# supply_test.net
KiCad netlist of a schematic drawn in EAGLE
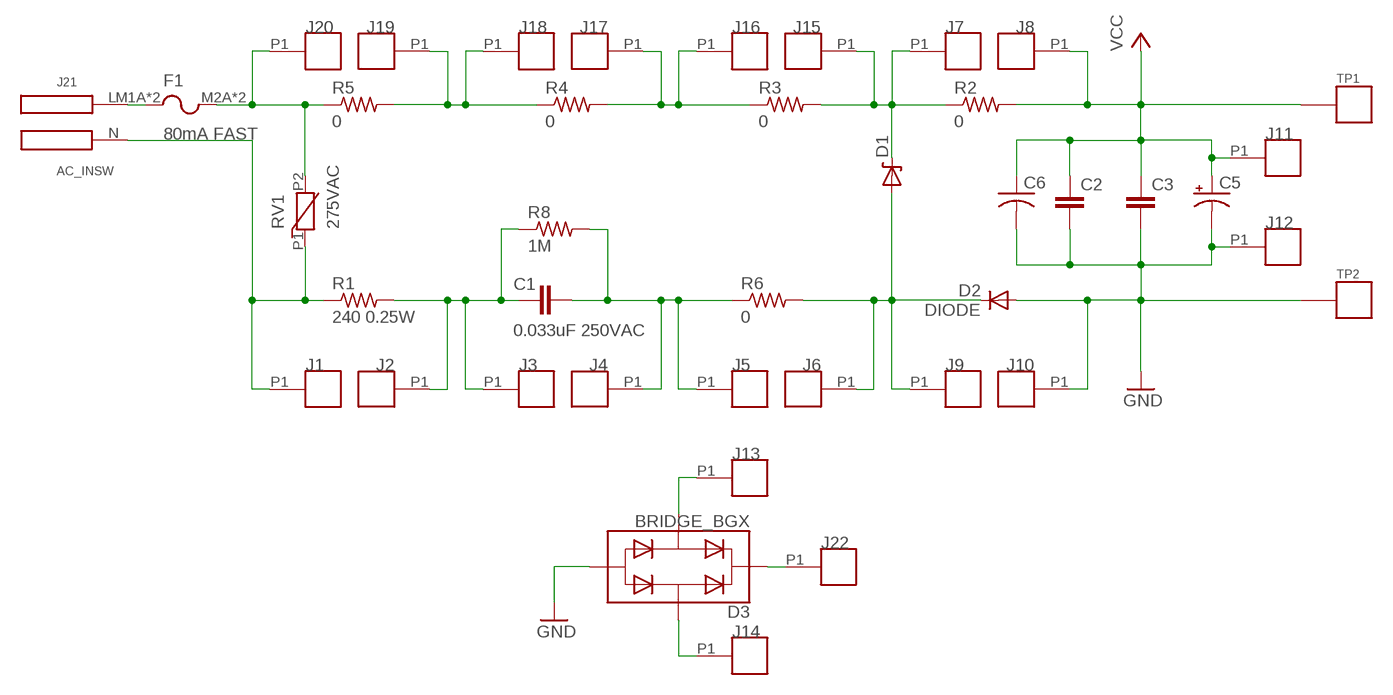
[diagram p0: schematic, sheet 1]
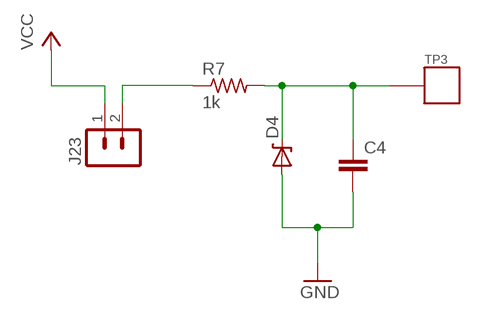
[diagram p1: schematic, sheet 2]

(export (version "E")
  (design (tool "Eeschema 10.0.6"))
  (components
    (comp (ref "C4")
      (value "C-EUC0603")
      (footprint "eagle-import:C0603")
      (libsource (lib "eagle-import") (part "C-EUC0603"))
    )
    (comp (ref "D4")
      (value "ZENERBZT52")
      (footprint "eagle-import:BZT52")
      (libsource (lib "eagle-import") (part "ZENERBZT52"))
    )
    (comp (ref "J23")
      (value "MA02-1STR")
      (footprint "eagle-import:MA02-1")
      (libsource (lib "eagle-import") (part "MA02-1STR"))
    )
    (comp (ref "R7")
      (value "1k")
      (footprint "eagle-import:R0603")
      (libsource (lib "eagle-import") (part "R-US_R0603"))
    )
    (comp (ref "TP3")
      (value "TP_STD")
      (footprint "eagle-import:TP")
      (libsource (lib "eagle-import") (part "TP_STD"))
    )
    (comp (ref "C1")
      (value "0.033uF 250VAC")
      (footprint "eagle-import:C2220K")
      (libsource (lib "eagle-import") (part "C-EUC2220K"))
    )
    (comp (ref "C2")
      (value "C-EUC0805")
      (footprint "eagle-import:C0805")
      (libsource (lib "eagle-import") (part "C-EUC0805"))
    )
    (comp (ref "C3")
      (value "C-EUC0603")
      (footprint "eagle-import:C0603")
      (libsource (lib "eagle-import") (part "C-EUC0603"))
    )
    (comp (ref "C5")
      (value "CAP_POL1206")
      (footprint "eagle-import:EIA3216")
      (libsource (lib "eagle-import") (part "CAP_POL1206"))
    )
    (comp (ref "C6")
      (value "C-USC1210")
      (footprint "eagle-import:C1210")
      (libsource (lib "eagle-import") (part "C-USC1210"))
    )
    (comp (ref "D1")
      (value "ZENERBZT52")
      (footprint "eagle-import:BZT52")
      (libsource (lib "eagle-import") (part "ZENERBZT52"))
    )
    (comp (ref "D2")
      (value "DIODE")
      (footprint "eagle-import:BAS521")
      (libsource (lib "eagle-import") (part "DIODE"))
    )
    (comp (ref "D3")
      (value "BRIDGE_BGX")
      (footprint "eagle-import:TO-253-4")
      (libsource (lib "eagle-import") (part "BRIDGE_BGX"))
    )
    (comp (ref "F1")
      (value "80mA FAST")
      (footprint "eagle-import:FUSE")
      (libsource (lib "eagle-import") (part "FUSE"))
    )
    (comp (ref "J1")
      (value "SOCKET")
      (footprint "eagle-import:SOCKET_1MM")
      (libsource (lib "eagle-import") (part "SOCKET"))
    )
    (comp (ref "J2")
      (value "SOCKET")
      (footprint "eagle-import:SOCKET_1MM")
      (libsource (lib "eagle-import") (part "SOCKET"))
    )
    (comp (ref "J3")
      (value "SOCKET")
      (footprint "eagle-import:SOCKET_1MM")
      (libsource (lib "eagle-import") (part "SOCKET"))
    )
    (comp (ref "J4")
      (value "SOCKET")
      (footprint "eagle-import:SOCKET_1MM")
      (libsource (lib "eagle-import") (part "SOCKET"))
    )
    (comp (ref "J5")
      (value "SOCKET")
      (footprint "eagle-import:SOCKET_1MM")
      (libsource (lib "eagle-import") (part "SOCKET"))
    )
    (comp (ref "J6")
      (value "SOCKET")
      (footprint "eagle-import:SOCKET_1MM")
      (libsource (lib "eagle-import") (part "SOCKET"))
    )
    (comp (ref "J7")
      (value "SOCKET")
      (footprint "eagle-import:SOCKET_1MM")
      (libsource (lib "eagle-import") (part "SOCKET"))
    )
    (comp (ref "J8")
      (value "SOCKET")
      (footprint "eagle-import:SOCKET_1MM")
      (libsource (lib "eagle-import") (part "SOCKET"))
    )
    (comp (ref "J9")
      (value "SOCKET")
      (footprint "eagle-import:SOCKET_1MM")
      (libsource (lib "eagle-import") (part "SOCKET"))
    )
    (comp (ref "J10")
      (value "SOCKET")
      (footprint "eagle-import:SOCKET_1MM")
      (libsource (lib "eagle-import") (part "SOCKET"))
    )
    (comp (ref "J11")
      (value "SOCKET")
      (footprint "eagle-import:SOCKET_1MM")
      (libsource (lib "eagle-import") (part "SOCKET"))
    )
    (comp (ref "J12")
      (value "SOCKET")
      (footprint "eagle-import:SOCKET_1MM")
      (libsource (lib "eagle-import") (part "SOCKET"))
    )
    (comp (ref "J13")
      (value "SOCKET")
      (footprint "eagle-import:SOCKET_1MM")
      (fields (field (name "DIGIKEY") "ED90076-ND"))
      (libsource (lib "eagle-import") (part "SOCKET"))
    )
    (comp (ref "J14")
      (value "SOCKET")
      (footprint "eagle-import:SOCKET_1MM")
      (fields (field (name "DIGIKEY") "ED90076-ND"))
      (libsource (lib "eagle-import") (part "SOCKET"))
    )
    (comp (ref "J15")
      (value "SOCKET")
      (footprint "eagle-import:SOCKET_1MM")
      (libsource (lib "eagle-import") (part "SOCKET"))
    )
    (comp (ref "J16")
      (value "SOCKET")
      (footprint "eagle-import:SOCKET_1MM")
      (libsource (lib "eagle-import") (part "SOCKET"))
    )
    (comp (ref "J17")
      (value "SOCKET")
      (footprint "eagle-import:SOCKET_1MM")
      (libsource (lib "eagle-import") (part "SOCKET"))
    )
    (comp (ref "J18")
      (value "SOCKET")
      (footprint "eagle-import:SOCKET_1MM")
      (libsource (lib "eagle-import") (part "SOCKET"))
    )
    (comp (ref "J19")
      (value "SOCKET")
      (footprint "eagle-import:SOCKET_1MM")
      (libsource (lib "eagle-import") (part "SOCKET"))
    )
    (comp (ref "J20")
      (value "SOCKET")
      (footprint "eagle-import:SOCKET_1MM")
      (libsource (lib "eagle-import") (part "SOCKET"))
    )
    (comp (ref "J21")
      (value "AC_INSW")
      (footprint "eagle-import:AC_DC21")
      (libsource (lib "eagle-import") (part "AC_INSW"))
    )
    (comp (ref "J22")
      (value "SOCKET")
      (footprint "eagle-import:SOCKET_1MM")
      (fields (field (name "DIGIKEY") "ED90076-ND"))
      (libsource (lib "eagle-import") (part "SOCKET"))
    )
    (comp (ref "R1")
      (value "240 0.25W")
      (footprint "eagle-import:R0603")
      (libsource (lib "eagle-import") (part "R-US_R0603"))
    )
    (comp (ref "R2")
      (value "0")
      (footprint "eagle-import:R0603")
      (libsource (lib "eagle-import") (part "R-US_R0603"))
    )
    (comp (ref "R3")
      (value "0")
      (footprint "eagle-import:R0603")
      (libsource (lib "eagle-import") (part "R-US_R0603"))
    )
    (comp (ref "R4")
      (value "0")
      (footprint "eagle-import:R0603")
      (libsource (lib "eagle-import") (part "R-US_R0603"))
    )
    (comp (ref "R5")
      (value "0")
      (footprint "eagle-import:R0603")
      (libsource (lib "eagle-import") (part "R-US_R0603"))
    )
    (comp (ref "R6")
      (value "0")
      (footprint "eagle-import:R0603")
      (libsource (lib "eagle-import") (part "R-US_R0603"))
    )
    (comp (ref "R8")
      (value "1M")
      (footprint "eagle-import:R0603")
      (libsource (lib "eagle-import") (part "R-US_R0603"))
    )
    (comp (ref "RV1")
      (value "275VAC")
      (footprint "eagle-import:MOV_4032")
      (libsource (lib "eagle-import") (part "MOV_CU4032"))
    )
    (comp (ref "TP1")
      (value "TP_STD")
      (footprint "eagle-import:TP")
      (libsource (lib "eagle-import") (part "TP_STD"))
    )
    (comp (ref "TP2")
      (value "TP_STD")
      (footprint "eagle-import:TP")
      (libsource (lib "eagle-import") (part "TP_STD"))
    )
  )
  (nets
    (net (code "1") (name "GND") (class "Default")
      (node (ref "C2") (pin "2") (pinfunction "2_2") (pintype "passive"))
      (node (ref "C3") (pin "2") (pinfunction "2_2") (pintype "passive"))
      (node (ref "C4") (pin "2") (pinfunction "2_2") (pintype "passive"))
      (node (ref "C5") (pin "C") (pinfunction "-_C") (pintype "passive"))
      (node (ref "C6") (pin "2") (pinfunction "2_2") (pintype "passive"))
      (node (ref "D2") (pin "A") (pinfunction "A_A") (pintype "passive"))
      (node (ref "D3") (pin "P3") (pinfunction "P3_P3") (pintype "passive"))
      (node (ref "D4") (pin "A") (pinfunction "A_A") (pintype "passive"))
      (node (ref "J10") (pin "P1") (pinfunction "P1_P1") (pintype "bidirectional"))
      (node (ref "J12") (pin "P1") (pinfunction "P1_P1") (pintype "bidirectional"))
      (node (ref "TP2") (pin "P$1") (pinfunction "P$1_P$1") (pintype "bidirectional"))
    )
    (net (code "2") (name "Net-(C1-Pad1)") (class "Default")
      (node (ref "C1") (pin "1") (pinfunction "1_1") (pintype "passive"))
      (node (ref "J4") (pin "P1") (pinfunction "P1_P1") (pintype "bidirectional"))
      (node (ref "J5") (pin "P1") (pinfunction "P1_P1") (pintype "bidirectional"))
      (node (ref "R6") (pin "1") (pinfunction "1_1") (pintype "passive"))
      (node (ref "R8") (pin "2") (pinfunction "2_2") (pintype "passive"))
    )
    (net (code "3") (name "Net-(C1-Pad2)") (class "Default")
      (node (ref "C1") (pin "2") (pinfunction "2_2") (pintype "passive"))
      (node (ref "J2") (pin "P1") (pinfunction "P1_P1") (pintype "bidirectional"))
      (node (ref "J3") (pin "P1") (pinfunction "P1_P1") (pintype "bidirectional"))
      (node (ref "R1") (pin "2") (pinfunction "2_2") (pintype "passive"))
      (node (ref "R8") (pin "1") (pinfunction "1_1") (pintype "passive"))
    )
    (net (code "4") (name "Net-(C4-Pad1)") (class "Default")
      (node (ref "C4") (pin "1") (pinfunction "1_1") (pintype "passive"))
      (node (ref "D4") (pin "C") (pinfunction "C_C") (pintype "passive"))
      (node (ref "R7") (pin "2") (pinfunction "2_2") (pintype "passive"))
      (node (ref "TP3") (pin "P$1") (pinfunction "P$1_P$1") (pintype "bidirectional"))
    )
    (net (code "5") (name "Net-(D1-PadA)") (class "Default")
      (node (ref "D1") (pin "A") (pinfunction "A_A") (pintype "passive"))
      (node (ref "D2") (pin "C") (pinfunction "C_C") (pintype "passive"))
      (node (ref "J6") (pin "P1") (pinfunction "P1_P1") (pintype "bidirectional"))
      (node (ref "J9") (pin "P1") (pinfunction "P1_P1") (pintype "bidirectional"))
      (node (ref "R6") (pin "2") (pinfunction "2_2") (pintype "passive"))
    )
    (net (code "6") (name "Net-(D1-PadC)") (class "Default")
      (node (ref "D1") (pin "C") (pinfunction "C_C") (pintype "passive"))
      (node (ref "J15") (pin "P1") (pinfunction "P1_P1") (pintype "bidirectional"))
      (node (ref "J7") (pin "P1") (pinfunction "P1_P1") (pintype "bidirectional"))
      (node (ref "R2") (pin "1") (pinfunction "1_1") (pintype "passive"))
      (node (ref "R3") (pin "2") (pinfunction "2_2") (pintype "passive"))
    )
    (net (code "7") (name "Net-(D3-PadP1)") (class "Default")
      (node (ref "D3") (pin "P1") (pinfunction "P1_P1") (pintype "passive"))
      (node (ref "J22") (pin "P1") (pinfunction "P1_P1") (pintype "bidirectional"))
    )
    (net (code "8") (name "Net-(D3-PadP2)") (class "Default")
      (node (ref "D3") (pin "P2") (pinfunction "P2_P2") (pintype "passive"))
      (node (ref "J13") (pin "P1") (pinfunction "P1_P1") (pintype "bidirectional"))
    )
    (net (code "9") (name "Net-(D3-PadP4)") (class "Default")
      (node (ref "D3") (pin "P4") (pinfunction "P4_P4") (pintype "passive"))
      (node (ref "J14") (pin "P1") (pinfunction "P1_P1") (pintype "bidirectional"))
    )
    (net (code "10") (name "Net-(F1-P2-PadM2A)") (class "Default")
      (node (ref "F1") (pin "M2A") (pinfunction "P2_M2A") (pintype "bidirectional"))
      (node (ref "F1") (pin "M2B") (pinfunction "P2_M2B") (pintype "bidirectional"))
      (node (ref "J20") (pin "P1") (pinfunction "P1_P1") (pintype "bidirectional"))
      (node (ref "R5") (pin "1") (pinfunction "1_1") (pintype "passive"))
      (node (ref "RV1") (pin "P2") (pinfunction "P2_P2") (pintype "bidirectional"))
    )
    (net (code "11") (name "Net-(J1-PadP1)") (class "Default")
      (node (ref "J1") (pin "P1") (pinfunction "P1_P1") (pintype "bidirectional"))
      (node (ref "J21") (pin "N") (pinfunction "N_N") (pintype "bidirectional"))
      (node (ref "R1") (pin "1") (pinfunction "1_1") (pintype "passive"))
      (node (ref "RV1") (pin "P1") (pinfunction "P1_P1") (pintype "bidirectional"))
    )
    (net (code "12") (name "Net-(J16-PadP1)") (class "Default")
      (node (ref "J16") (pin "P1") (pinfunction "P1_P1") (pintype "bidirectional"))
      (node (ref "J17") (pin "P1") (pinfunction "P1_P1") (pintype "bidirectional"))
      (node (ref "R3") (pin "1") (pinfunction "1_1") (pintype "passive"))
      (node (ref "R4") (pin "2") (pinfunction "2_2") (pintype "passive"))
    )
    (net (code "13") (name "Net-(J18-PadP1)") (class "Default")
      (node (ref "J18") (pin "P1") (pinfunction "P1_P1") (pintype "bidirectional"))
      (node (ref "J19") (pin "P1") (pinfunction "P1_P1") (pintype "bidirectional"))
      (node (ref "R4") (pin "1") (pinfunction "1_1") (pintype "passive"))
      (node (ref "R5") (pin "2") (pinfunction "2_2") (pintype "passive"))
    )
    (net (code "14") (name "Net-(J21-P)") (class "Default")
      (node (ref "F1") (pin "M1A") (pinfunction "P1_M1A") (pintype "bidirectional"))
      (node (ref "F1") (pin "M1B") (pinfunction "P1_M1B") (pintype "bidirectional"))
      (node (ref "J21") (pin "L") (pinfunction "P_L") (pintype "bidirectional"))
    )
    (net (code "15") (name "Net-(J23-Pad2)") (class "Default")
      (node (ref "J23") (pin "2") (pinfunction "2_2") (pintype "passive"))
      (node (ref "R7") (pin "1") (pinfunction "1_1") (pintype "passive"))
    )
    (net (code "16") (name "VCC") (class "Default")
      (node (ref "C2") (pin "1") (pinfunction "1_1") (pintype "passive"))
      (node (ref "C3") (pin "1") (pinfunction "1_1") (pintype "passive"))
      (node (ref "C5") (pin "A") (pinfunction "+_A") (pintype "passive"))
      (node (ref "C6") (pin "1") (pinfunction "1_1") (pintype "passive"))
      (node (ref "J11") (pin "P1") (pinfunction "P1_P1") (pintype "bidirectional"))
      (node (ref "J23") (pin "1") (pinfunction "1_1") (pintype "passive"))
      (node (ref "J8") (pin "P1") (pinfunction "P1_P1") (pintype "bidirectional"))
      (node (ref "R2") (pin "2") (pinfunction "2_2") (pintype "passive"))
      (node (ref "TP1") (pin "P$1") (pinfunction "P$1_P$1") (pintype "bidirectional"))
    )
  )
)
